# SCH_SemaforkyNG_EasyEDA.net
KiCad netlist of a schematic drawn in EasyEDA
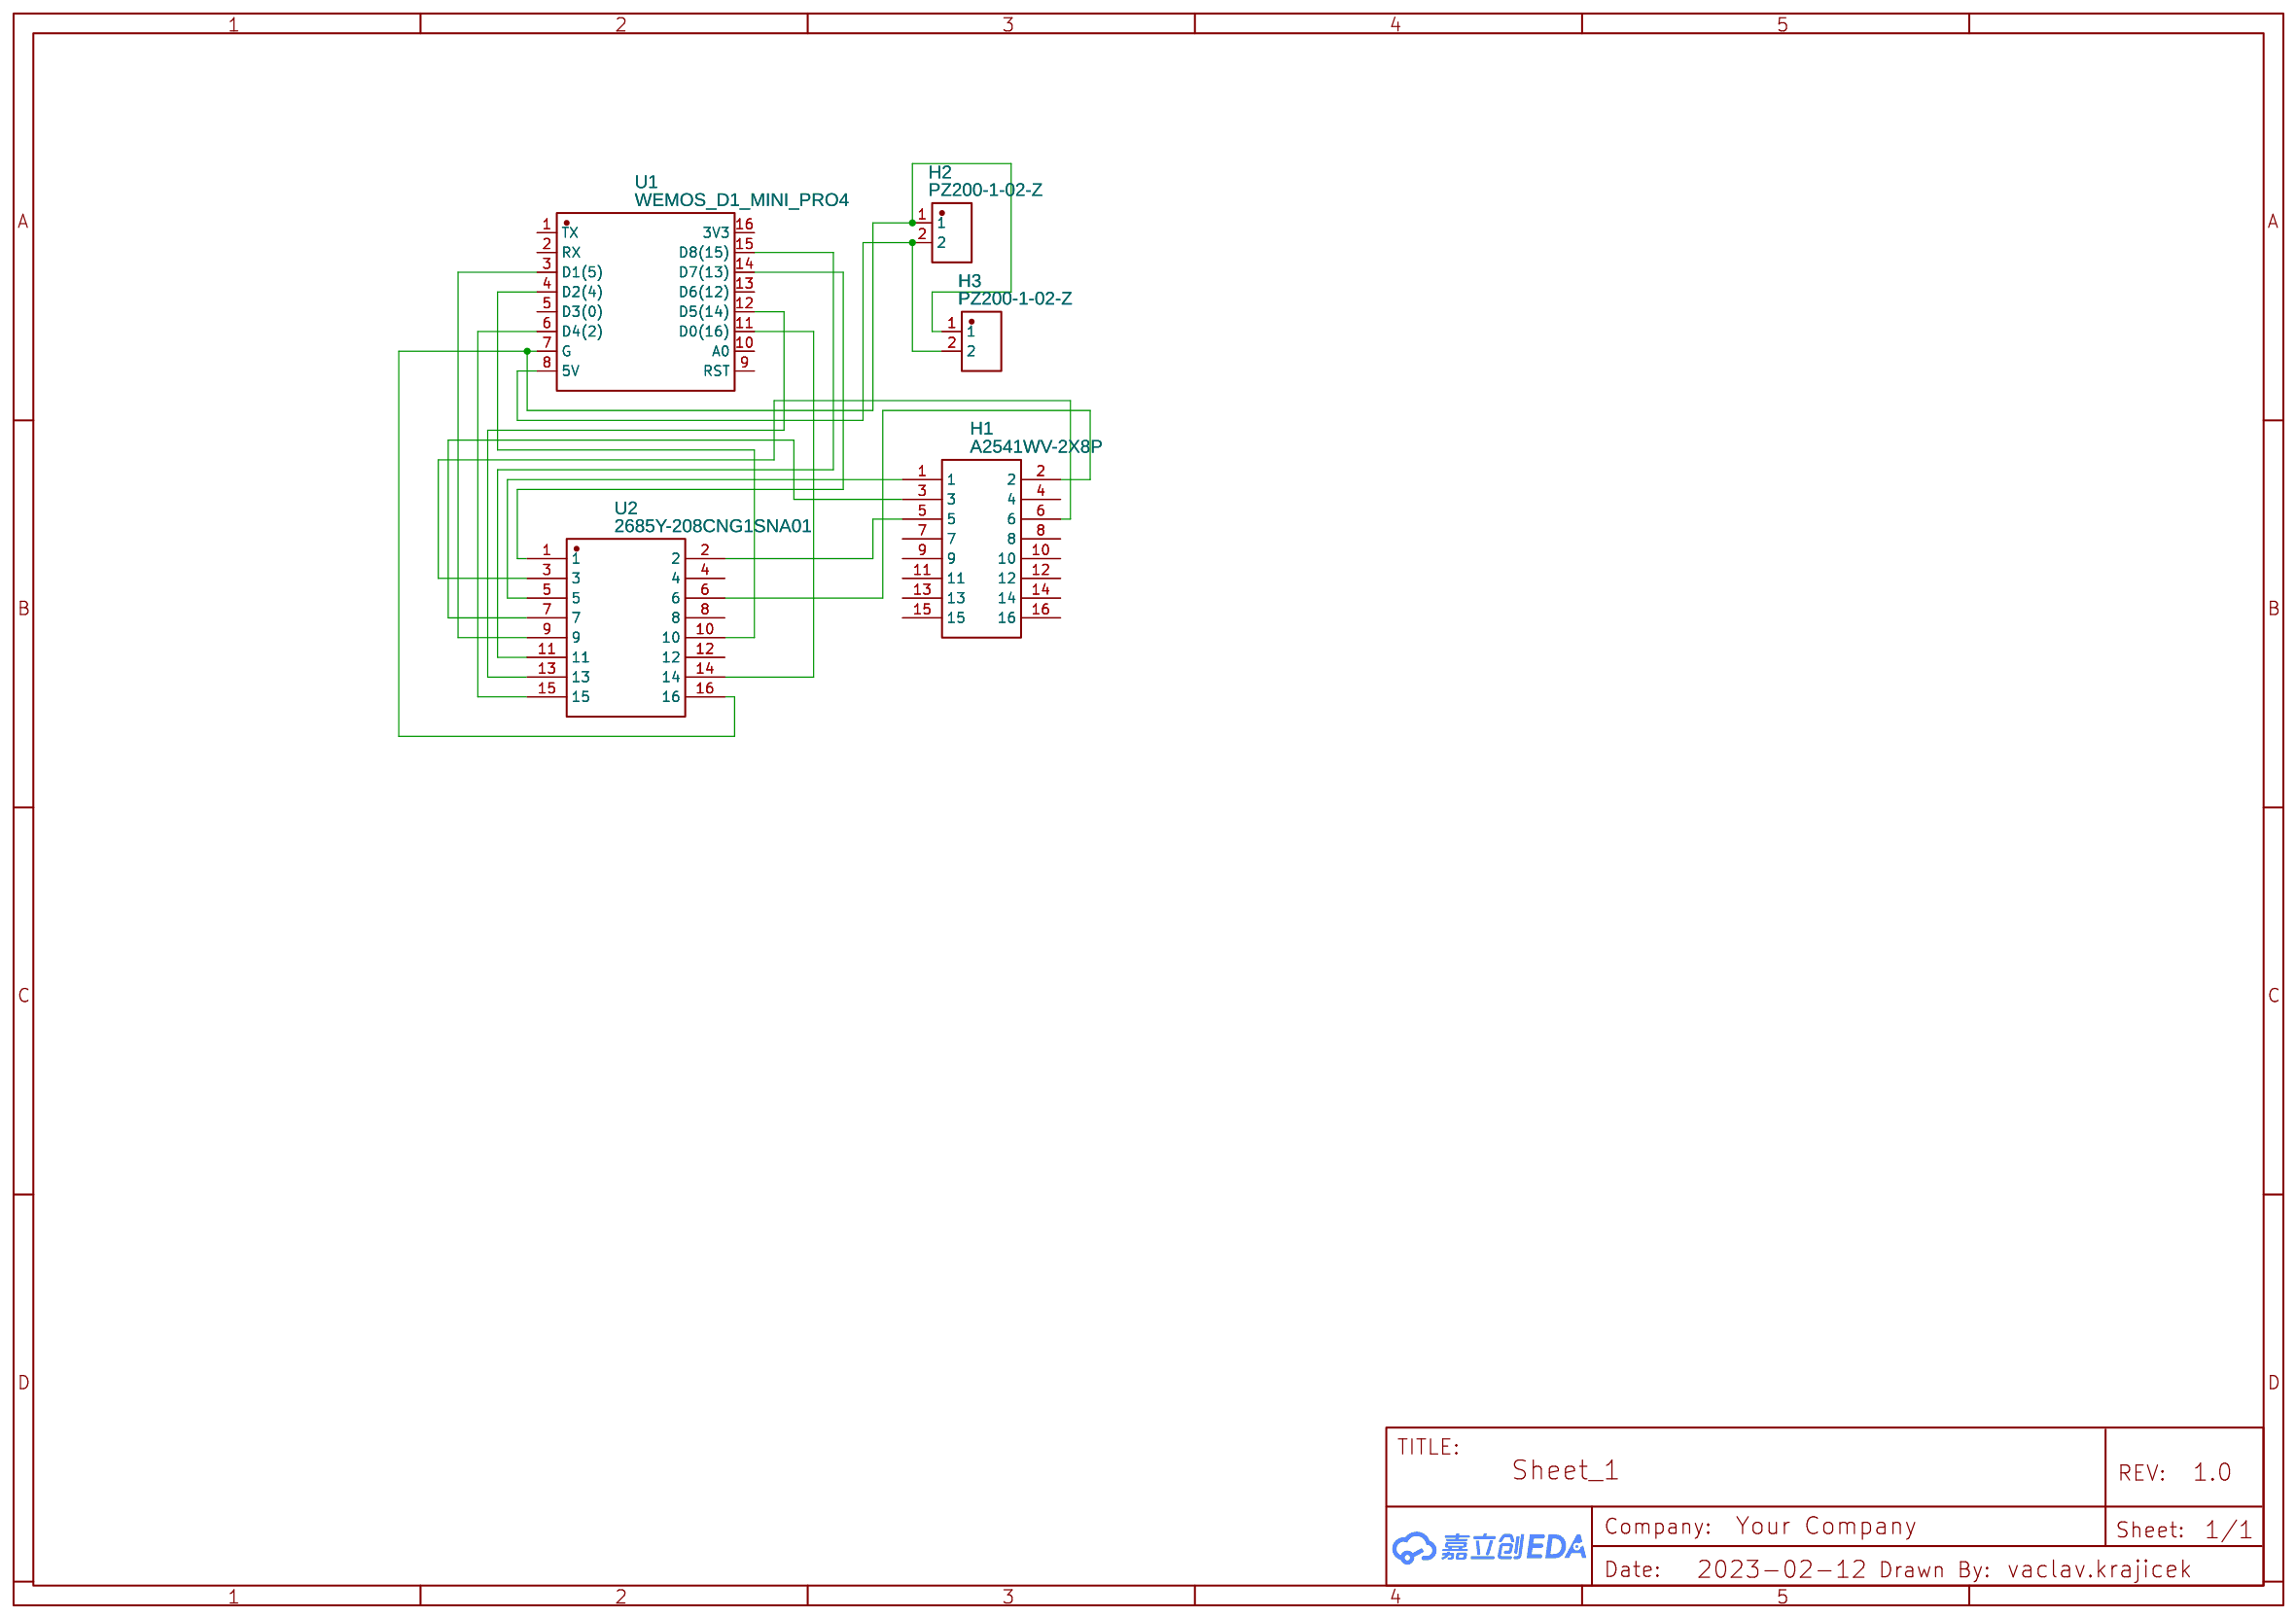
[diagram p0: schematic sheet]

(export (version "E")
  (design (tool "Eeschema 10.0.6"))
  (components
    (comp (ref "H1")
      (value "A2541WV-2X8P")
      (fields
        (field (name "BOM_Manufacturer Part") "A2541WV-2x8P")
        (field (name "BOM_Supplier Part") "C225523")
      )
      (libsource (lib "") (part "A2541WV-2X8P"))
    )
    (comp (ref "H2")
      (value "PZ200-1-02-Z")
      (fields (field (name "BOM_Supplier Part") "C2905948"))
      (libsource (lib "") (part "PZ200-1-02-Z"))
    )
    (comp (ref "H3")
      (value "PZ200-1-02-Z")
      (fields (field (name "BOM_Supplier Part") "C2905948"))
      (libsource (lib "") (part "PZ200-1-02-Z"))
    )
    (comp (ref "U1")
      (value "WEMOS_D1_MINI_PRO4")
      (fields
        (field (name "BOM_Manufacturer Part") "Wemos_D1_mini_Pro4")
        (field (name "BOM_Supplier Part") "C2837266")
      )
      (libsource (lib "") (part "WEMOS_D1_MINI_PRO4"))
    )
    (comp (ref "U2")
      (value "2685Y-208CNG1SNA01")
      (fields (field (name "BOM_Supplier Part") "C350292"))
      (libsource (lib "") (part "2685Y-208CNG1SNA01"))
    )
  )
  (nets
    (net (code "1") (name "Net-(H1-Pad1)") (class "Default")
      (node (ref "H1") (pin "1") (pinfunction "1_1") (pintype "unspecified"))
      (node (ref "U2") (pin "5") (pinfunction "5_5") (pintype "unspecified"))
    )
    (net (code "2") (name "Net-(H1-Pad2)") (class "Default")
      (node (ref "H1") (pin "2") (pinfunction "2_2") (pintype "unspecified"))
      (node (ref "U2") (pin "6") (pinfunction "6_6") (pintype "unspecified"))
    )
    (net (code "3") (name "Net-(H1-Pad3)") (class "Default")
      (node (ref "H1") (pin "3") (pinfunction "3_3") (pintype "unspecified"))
      (node (ref "U2") (pin "7") (pinfunction "7_7") (pintype "unspecified"))
    )
    (net (code "4") (name "Net-(H1-Pad5)") (class "Default")
      (node (ref "H1") (pin "5") (pinfunction "5_5") (pintype "unspecified"))
      (node (ref "U2") (pin "2") (pinfunction "2_2") (pintype "unspecified"))
    )
    (net (code "5") (name "Net-(H1-Pad6)") (class "Default")
      (node (ref "H1") (pin "6") (pinfunction "6_6") (pintype "unspecified"))
      (node (ref "U2") (pin "3") (pinfunction "3_3") (pintype "unspecified"))
    )
    (net (code "6") (name "Net-(U1-5V)") (class "Default")
      (node (ref "H2") (pin "2") (pinfunction "2_2") (pintype "unspecified"))
      (node (ref "H3") (pin "2") (pinfunction "2_2") (pintype "unspecified"))
      (node (ref "U1") (pin "8") (pinfunction "5V_8") (pintype "unspecified"))
    )
    (net (code "7") (name "Net-(U1-D0(16))") (class "Default")
      (node (ref "U1") (pin "11") (pinfunction "D0(16)_11") (pintype "unspecified"))
      (node (ref "U2") (pin "14") (pinfunction "14_14") (pintype "unspecified"))
    )
    (net (code "8") (name "Net-(U1-D1(5))") (class "Default")
      (node (ref "U1") (pin "3") (pinfunction "D1(5)_3") (pintype "unspecified"))
      (node (ref "U2") (pin "9") (pinfunction "9_9") (pintype "unspecified"))
    )
    (net (code "9") (name "Net-(U1-D2(4))") (class "Default")
      (node (ref "U1") (pin "4") (pinfunction "D2(4)_4") (pintype "unspecified"))
      (node (ref "U2") (pin "10") (pinfunction "10_10") (pintype "unspecified"))
    )
    (net (code "10") (name "Net-(U1-D4(2))") (class "Default")
      (node (ref "U1") (pin "6") (pinfunction "D4(2)_6") (pintype "unspecified"))
      (node (ref "U2") (pin "15") (pinfunction "15_15") (pintype "unspecified"))
    )
    (net (code "11") (name "Net-(U1-D5(14))") (class "Default")
      (node (ref "U1") (pin "12") (pinfunction "D5(14)_12") (pintype "unspecified"))
      (node (ref "U2") (pin "13") (pinfunction "13_13") (pintype "unspecified"))
    )
    (net (code "12") (name "Net-(U1-D7(13))") (class "Default")
      (node (ref "U1") (pin "14") (pinfunction "D7(13)_14") (pintype "unspecified"))
      (node (ref "U2") (pin "1") (pinfunction "1_1") (pintype "unspecified"))
    )
    (net (code "13") (name "Net-(U1-D8(15))") (class "Default")
      (node (ref "U1") (pin "15") (pinfunction "D8(15)_15") (pintype "unspecified"))
      (node (ref "U2") (pin "11") (pinfunction "11_11") (pintype "unspecified"))
    )
    (net (code "14") (name "Net-(U1-G)") (class "Default")
      (node (ref "H2") (pin "1") (pinfunction "1_1") (pintype "unspecified"))
      (node (ref "H3") (pin "1") (pinfunction "1_1") (pintype "unspecified"))
      (node (ref "U1") (pin "7") (pinfunction "G_7") (pintype "unspecified"))
      (node (ref "U2") (pin "16") (pinfunction "16_16") (pintype "unspecified"))
    )
    (net (code "15") (name "unconnected-(H1-Pad4)") (class "Default")
      (node (ref "H1") (pin "4") (pinfunction "4_4") (pintype "unspecified"))
    )
    (net (code "16") (name "unconnected-(H1-Pad7)") (class "Default")
      (node (ref "H1") (pin "7") (pinfunction "7_7") (pintype "unspecified"))
    )
    (net (code "17") (name "unconnected-(H1-Pad8)") (class "Default")
      (node (ref "H1") (pin "8") (pinfunction "8_8") (pintype "unspecified"))
    )
    (net (code "18") (name "unconnected-(H1-Pad9)") (class "Default")
      (node (ref "H1") (pin "9") (pinfunction "9_9") (pintype "unspecified"))
    )
    (net (code "19") (name "unconnected-(H1-Pad10)") (class "Default")
      (node (ref "H1") (pin "10") (pinfunction "10_10") (pintype "unspecified"))
    )
    (net (code "20") (name "unconnected-(H1-Pad11)") (class "Default")
      (node (ref "H1") (pin "11") (pinfunction "11_11") (pintype "unspecified"))
    )
    (net (code "21") (name "unconnected-(H1-Pad12)") (class "Default")
      (node (ref "H1") (pin "12") (pinfunction "12_12") (pintype "unspecified"))
    )
    (net (code "22") (name "unconnected-(H1-Pad13)") (class "Default")
      (node (ref "H1") (pin "13") (pinfunction "13_13") (pintype "unspecified"))
    )
    (net (code "23") (name "unconnected-(H1-Pad14)") (class "Default")
      (node (ref "H1") (pin "14") (pinfunction "14_14") (pintype "unspecified"))
    )
    (net (code "24") (name "unconnected-(H1-Pad15)") (class "Default")
      (node (ref "H1") (pin "15") (pinfunction "15_15") (pintype "unspecified"))
    )
    (net (code "25") (name "unconnected-(H1-Pad16)") (class "Default")
      (node (ref "H1") (pin "16") (pinfunction "16_16") (pintype "unspecified"))
    )
    (net (code "26") (name "unconnected-(U1-3V3-Pad16)") (class "Default")
      (node (ref "U1") (pin "16") (pinfunction "3V3_16") (pintype "unspecified"))
    )
    (net (code "27") (name "unconnected-(U1-A0-Pad10)") (class "Default")
      (node (ref "U1") (pin "10") (pinfunction "A0_10") (pintype "unspecified"))
    )
    (net (code "28") (name "unconnected-(U1-D3(0)-Pad5)") (class "Default")
      (node (ref "U1") (pin "5") (pinfunction "D3(0)_5") (pintype "unspecified"))
    )
    (net (code "29") (name "unconnected-(U1-D6(12)-Pad13)") (class "Default")
      (node (ref "U1") (pin "13") (pinfunction "D6(12)_13") (pintype "unspecified"))
    )
    (net (code "30") (name "unconnected-(U1-RST-Pad9)") (class "Default")
      (node (ref "U1") (pin "9") (pinfunction "RST_9") (pintype "unspecified"))
    )
    (net (code "31") (name "unconnected-(U1-RX-Pad2)") (class "Default")
      (node (ref "U1") (pin "2") (pinfunction "RX_2") (pintype "unspecified"))
    )
    (net (code "32") (name "unconnected-(U1-TX-Pad1)") (class "Default")
      (node (ref "U1") (pin "1") (pinfunction "TX_1") (pintype "unspecified"))
    )
    (net (code "33") (name "unconnected-(U2-Pad4)") (class "Default")
      (node (ref "U2") (pin "4") (pinfunction "4_4") (pintype "unspecified"))
    )
    (net (code "34") (name "unconnected-(U2-Pad8)") (class "Default")
      (node (ref "U2") (pin "8") (pinfunction "8_8") (pintype "unspecified"))
    )
    (net (code "35") (name "unconnected-(U2-Pad12)") (class "Default")
      (node (ref "U2") (pin "12") (pinfunction "12_12") (pintype "unspecified"))
    )
  )
)
